# Light_Board.net
KiCad netlist of a schematic drawn in Altium Designer
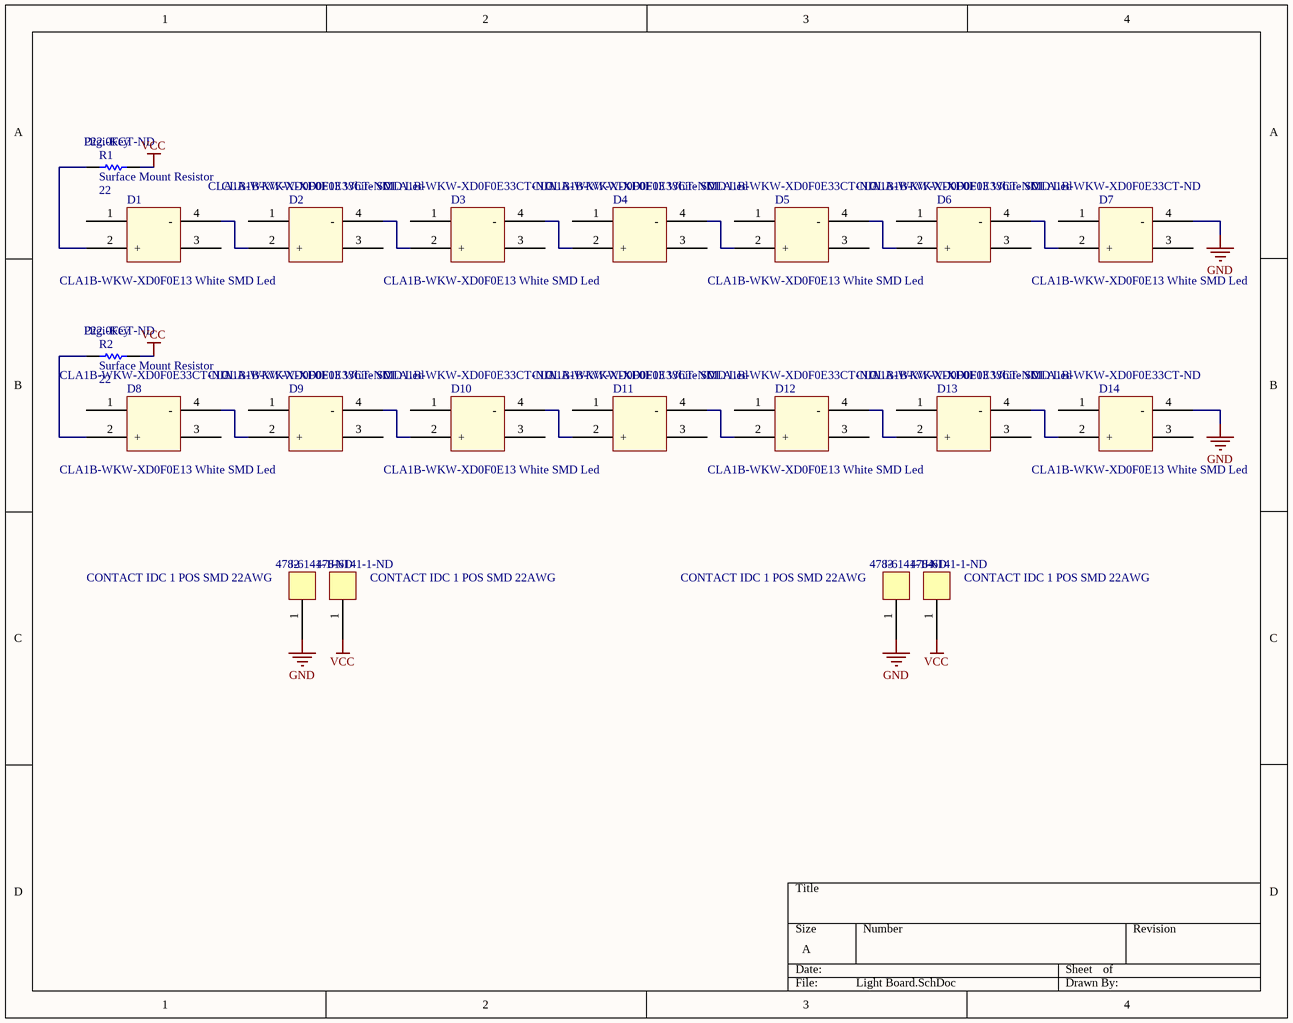
[diagram p0: Light Board.SchDoc]

(export (version "E")
  (design (tool "Eeschema 10.0.6"))
  (components
    (comp (ref "D1")
      (value "CLA1B-WKW-XD0F0E13 White SMD Led")
      (footprint "CLA1B-WKW-XD0F0E13 White SMD Led")
      (libsource (lib "Light Board") (part "CLA1B-WKW-XD0F0E13 White SMD Led"))
    )
    (comp (ref "D2")
      (value "CLA1B-WKW-XD0F0E13 White SMD Led")
      (footprint "CLA1B-WKW-XD0F0E13 White SMD Led")
      (fields (field (name "SUPPLIER PART NUMBER 1") "CLA1B-WKW-XD0F0E33CT-ND"))
      (libsource (lib "Light Board") (part "CLA1B-WKW-XD0F0E13 White SMD Led"))
    )
    (comp (ref "D3")
      (value "CLA1B-WKW-XD0F0E13 White SMD Led")
      (footprint "CLA1B-WKW-XD0F0E13 White SMD Led")
      (fields (field (name "SUPPLIER PART NUMBER 1") "CLA1B-WKW-XD0F0E33CT-ND"))
      (libsource (lib "Light Board") (part "CLA1B-WKW-XD0F0E13 White SMD Led"))
    )
    (comp (ref "D4")
      (value "CLA1B-WKW-XD0F0E13 White SMD Led")
      (footprint "CLA1B-WKW-XD0F0E13 White SMD Led")
      (fields (field (name "SUPPLIER PART NUMBER 1") "CLA1B-WKW-XD0F0E33CT-ND"))
      (libsource (lib "Light Board") (part "CLA1B-WKW-XD0F0E13 White SMD Led"))
    )
    (comp (ref "D5")
      (value "CLA1B-WKW-XD0F0E13 White SMD Led")
      (footprint "CLA1B-WKW-XD0F0E13 White SMD Led")
      (fields (field (name "SUPPLIER PART NUMBER 1") "CLA1B-WKW-XD0F0E33CT-ND"))
      (libsource (lib "Light Board") (part "CLA1B-WKW-XD0F0E13 White SMD Led"))
    )
    (comp (ref "D6")
      (value "CLA1B-WKW-XD0F0E13 White SMD Led")
      (footprint "CLA1B-WKW-XD0F0E13 White SMD Led")
      (fields (field (name "SUPPLIER PART NUMBER 1") "CLA1B-WKW-XD0F0E33CT-ND"))
      (libsource (lib "Light Board") (part "CLA1B-WKW-XD0F0E13 White SMD Led"))
    )
    (comp (ref "D7")
      (value "CLA1B-WKW-XD0F0E13 White SMD Led")
      (footprint "CLA1B-WKW-XD0F0E13 White SMD Led")
      (fields (field (name "SUPPLIER PART NUMBER 1") "CLA1B-WKW-XD0F0E33CT-ND"))
      (libsource (lib "Light Board") (part "CLA1B-WKW-XD0F0E13 White SMD Led"))
    )
    (comp (ref "D8")
      (value "CLA1B-WKW-XD0F0E13 White SMD Led")
      (footprint "CLA1B-WKW-XD0F0E13 White SMD Led")
      (fields (field (name "SUPPLIER PART NUMBER 1") "CLA1B-WKW-XD0F0E33CT-ND"))
      (libsource (lib "Light Board") (part "CLA1B-WKW-XD0F0E13 White SMD Led"))
    )
    (comp (ref "D9")
      (value "CLA1B-WKW-XD0F0E13 White SMD Led")
      (footprint "CLA1B-WKW-XD0F0E13 White SMD Led")
      (fields (field (name "SUPPLIER PART NUMBER 1") "CLA1B-WKW-XD0F0E33CT-ND"))
      (libsource (lib "Light Board") (part "CLA1B-WKW-XD0F0E13 White SMD Led"))
    )
    (comp (ref "D10")
      (value "CLA1B-WKW-XD0F0E13 White SMD Led")
      (footprint "CLA1B-WKW-XD0F0E13 White SMD Led")
      (fields (field (name "SUPPLIER PART NUMBER 1") "CLA1B-WKW-XD0F0E33CT-ND"))
      (libsource (lib "Light Board") (part "CLA1B-WKW-XD0F0E13 White SMD Led"))
    )
    (comp (ref "D11")
      (value "CLA1B-WKW-XD0F0E13 White SMD Led")
      (footprint "CLA1B-WKW-XD0F0E13 White SMD Led")
      (fields (field (name "SUPPLIER PART NUMBER 1") "CLA1B-WKW-XD0F0E33CT-ND"))
      (libsource (lib "Light Board") (part "CLA1B-WKW-XD0F0E13 White SMD Led"))
    )
    (comp (ref "D12")
      (value "CLA1B-WKW-XD0F0E13 White SMD Led")
      (footprint "CLA1B-WKW-XD0F0E13 White SMD Led")
      (fields (field (name "SUPPLIER PART NUMBER 1") "CLA1B-WKW-XD0F0E33CT-ND"))
      (libsource (lib "Light Board") (part "CLA1B-WKW-XD0F0E13 White SMD Led"))
    )
    (comp (ref "D13")
      (value "CLA1B-WKW-XD0F0E13 White SMD Led")
      (footprint "CLA1B-WKW-XD0F0E13 White SMD Led")
      (fields (field (name "SUPPLIER PART NUMBER 1") "CLA1B-WKW-XD0F0E33CT-ND"))
      (libsource (lib "Light Board") (part "CLA1B-WKW-XD0F0E13 White SMD Led"))
    )
    (comp (ref "D14")
      (value "CLA1B-WKW-XD0F0E13 White SMD Led")
      (footprint "CLA1B-WKW-XD0F0E13 White SMD Led")
      (fields (field (name "SUPPLIER PART NUMBER 1") "CLA1B-WKW-XD0F0E33CT-ND"))
      (libsource (lib "Light Board") (part "CLA1B-WKW-XD0F0E13 White SMD Led"))
    )
    (comp (ref "J1")
      (value "CONTACT IDC 1 POS SMD 22AWG")
      (footprint "CONTACT IDC 1 POS SMD 22AWG")
      (fields (field (name "SUPPLIER PART NUMBER 1") "478-6141-1-ND"))
      (libsource (lib "Light Board") (part "CONTACT IDC 1 POS SMD 22AWG"))
    )
    (comp (ref "J2")
      (value "CONTACT IDC 1 POS SMD 22AWG")
      (footprint "CONTACT IDC 1 POS SMD 22AWG")
      (fields (field (name "SUPPLIER PART NUMBER 1") "478-6141-1-ND"))
      (libsource (lib "Light Board") (part "CONTACT IDC 1 POS SMD 22AWG"))
    )
    (comp (ref "J3")
      (value "CONTACT IDC 1 POS SMD 22AWG")
      (footprint "CONTACT IDC 1 POS SMD 22AWG")
      (fields (field (name "SUPPLIER PART NUMBER 1") "478-6141-1-ND"))
      (libsource (lib "Light Board") (part "CONTACT IDC 1 POS SMD 22AWG"))
    )
    (comp (ref "J4")
      (value "CONTACT IDC 1 POS SMD 22AWG")
      (footprint "CONTACT IDC 1 POS SMD 22AWG")
      (fields (field (name "SUPPLIER PART NUMBER 1") "478-6141-1-ND"))
      (libsource (lib "Light Board") (part "CONTACT IDC 1 POS SMD 22AWG"))
    )
    (comp (ref "R1")
      (value "Surface Mount Resistor")
      (footprint "8-1206")
      (description "Resistor")
      (fields
        (field (name "ALTIUM_VALUE") "22")
        (field (name "SUPPLIER 1") "Digi-Key")
        (field (name "SUPPLIER PART NUMBER 1") "P22.0FCT-ND")
        (field (name "PUBLISHER") "Altium Limited")
      )
      (libsource (lib "Light Board") (part "Surface Mount Resistor"))
    )
    (comp (ref "R2")
      (value "Surface Mount Resistor")
      (footprint "8-1206")
      (description "Resistor")
      (fields
        (field (name "ALTIUM_VALUE") "22")
        (field (name "SUPPLIER 1") "Digi-Key")
        (field (name "SUPPLIER PART NUMBER 1") "P22.0FCT-ND")
        (field (name "PUBLISHER") "Altium Limited")
      )
      (libsource (lib "Light Board") (part "Surface Mount Resistor"))
    )
  )
  (nets
    (net (code "1") (name "GND") (class "Default")
      (node (ref "D14") (pin "4") (pinfunction "-_4") (pintype "passive"))
      (node (ref "D7") (pin "4") (pinfunction "-_4") (pintype "passive"))
      (node (ref "J2") (pin "1") (pinfunction "1_1") (pintype "passive"))
      (node (ref "J3") (pin "1") (pinfunction "1_1") (pintype "passive"))
    )
    (net (code "2") (name "Net-(D1-+)") (class "Default")
      (node (ref "D1") (pin "2") (pinfunction "+_2") (pintype "passive"))
      (node (ref "R1") (pin "1") (pinfunction "1_1") (pintype "passive"))
    )
    (net (code "3") (name "Net-(D1--)") (class "Default")
      (node (ref "D1") (pin "4") (pinfunction "-_4") (pintype "passive"))
      (node (ref "D2") (pin "2") (pinfunction "+_2") (pintype "passive"))
    )
    (net (code "4") (name "Net-(D2--)") (class "Default")
      (node (ref "D2") (pin "4") (pinfunction "-_4") (pintype "passive"))
      (node (ref "D3") (pin "2") (pinfunction "+_2") (pintype "passive"))
    )
    (net (code "5") (name "Net-(D3--)") (class "Default")
      (node (ref "D3") (pin "4") (pinfunction "-_4") (pintype "passive"))
      (node (ref "D4") (pin "2") (pinfunction "+_2") (pintype "passive"))
    )
    (net (code "6") (name "Net-(D4--)") (class "Default")
      (node (ref "D4") (pin "4") (pinfunction "-_4") (pintype "passive"))
      (node (ref "D5") (pin "2") (pinfunction "+_2") (pintype "passive"))
    )
    (net (code "7") (name "Net-(D5--)") (class "Default")
      (node (ref "D5") (pin "4") (pinfunction "-_4") (pintype "passive"))
      (node (ref "D6") (pin "2") (pinfunction "+_2") (pintype "passive"))
    )
    (net (code "8") (name "Net-(D6--)") (class "Default")
      (node (ref "D6") (pin "4") (pinfunction "-_4") (pintype "passive"))
      (node (ref "D7") (pin "2") (pinfunction "+_2") (pintype "passive"))
    )
    (net (code "9") (name "Net-(D8-+)") (class "Default")
      (node (ref "D8") (pin "2") (pinfunction "+_2") (pintype "passive"))
      (node (ref "R2") (pin "1") (pinfunction "1_1") (pintype "passive"))
    )
    (net (code "10") (name "Net-(D8--)") (class "Default")
      (node (ref "D8") (pin "4") (pinfunction "-_4") (pintype "passive"))
      (node (ref "D9") (pin "2") (pinfunction "+_2") (pintype "passive"))
    )
    (net (code "11") (name "Net-(D10-+)") (class "Default")
      (node (ref "D10") (pin "2") (pinfunction "+_2") (pintype "passive"))
      (node (ref "D9") (pin "4") (pinfunction "-_4") (pintype "passive"))
    )
    (net (code "12") (name "Net-(D10--)") (class "Default")
      (node (ref "D10") (pin "4") (pinfunction "-_4") (pintype "passive"))
      (node (ref "D11") (pin "2") (pinfunction "+_2") (pintype "passive"))
    )
    (net (code "13") (name "Net-(D11--)") (class "Default")
      (node (ref "D11") (pin "4") (pinfunction "-_4") (pintype "passive"))
      (node (ref "D12") (pin "2") (pinfunction "+_2") (pintype "passive"))
    )
    (net (code "14") (name "Net-(D12--)") (class "Default")
      (node (ref "D12") (pin "4") (pinfunction "-_4") (pintype "passive"))
      (node (ref "D13") (pin "2") (pinfunction "+_2") (pintype "passive"))
    )
    (net (code "15") (name "Net-(D13--)") (class "Default")
      (node (ref "D13") (pin "4") (pinfunction "-_4") (pintype "passive"))
      (node (ref "D14") (pin "2") (pinfunction "+_2") (pintype "passive"))
    )
    (net (code "16") (name "VCC") (class "Default")
      (node (ref "J1") (pin "1") (pinfunction "1_1") (pintype "passive"))
      (node (ref "J4") (pin "1") (pinfunction "1_1") (pintype "passive"))
      (node (ref "R1") (pin "2") (pinfunction "2_2") (pintype "passive"))
      (node (ref "R2") (pin "2") (pinfunction "2_2") (pintype "passive"))
    )
    (net (code "17") (name "unconnected-(D1-5-Pad1)") (class "Default")
      (node (ref "D1") (pin "1") (pinfunction "5_1") (pintype "passive"))
    )
    (net (code "18") (name "unconnected-(D1-Pad3)") (class "Default")
      (node (ref "D1") (pin "3") (pinfunction "3_3") (pintype "passive"))
    )
    (net (code "19") (name "unconnected-(D2-5-Pad1)") (class "Default")
      (node (ref "D2") (pin "1") (pinfunction "5_1") (pintype "passive"))
    )
    (net (code "20") (name "unconnected-(D2-Pad3)") (class "Default")
      (node (ref "D2") (pin "3") (pinfunction "3_3") (pintype "passive"))
    )
    (net (code "21") (name "unconnected-(D3-5-Pad1)") (class "Default")
      (node (ref "D3") (pin "1") (pinfunction "5_1") (pintype "passive"))
    )
    (net (code "22") (name "unconnected-(D3-Pad3)") (class "Default")
      (node (ref "D3") (pin "3") (pinfunction "3_3") (pintype "passive"))
    )
    (net (code "23") (name "unconnected-(D4-5-Pad1)") (class "Default")
      (node (ref "D4") (pin "1") (pinfunction "5_1") (pintype "passive"))
    )
    (net (code "24") (name "unconnected-(D4-Pad3)") (class "Default")
      (node (ref "D4") (pin "3") (pinfunction "3_3") (pintype "passive"))
    )
    (net (code "25") (name "unconnected-(D5-5-Pad1)") (class "Default")
      (node (ref "D5") (pin "1") (pinfunction "5_1") (pintype "passive"))
    )
    (net (code "26") (name "unconnected-(D5-Pad3)") (class "Default")
      (node (ref "D5") (pin "3") (pinfunction "3_3") (pintype "passive"))
    )
    (net (code "27") (name "unconnected-(D6-5-Pad1)") (class "Default")
      (node (ref "D6") (pin "1") (pinfunction "5_1") (pintype "passive"))
    )
    (net (code "28") (name "unconnected-(D6-Pad3)") (class "Default")
      (node (ref "D6") (pin "3") (pinfunction "3_3") (pintype "passive"))
    )
    (net (code "29") (name "unconnected-(D7-5-Pad1)") (class "Default")
      (node (ref "D7") (pin "1") (pinfunction "5_1") (pintype "passive"))
    )
    (net (code "30") (name "unconnected-(D7-Pad3)") (class "Default")
      (node (ref "D7") (pin "3") (pinfunction "3_3") (pintype "passive"))
    )
    (net (code "31") (name "unconnected-(D8-5-Pad1)") (class "Default")
      (node (ref "D8") (pin "1") (pinfunction "5_1") (pintype "passive"))
    )
    (net (code "32") (name "unconnected-(D8-Pad3)") (class "Default")
      (node (ref "D8") (pin "3") (pinfunction "3_3") (pintype "passive"))
    )
    (net (code "33") (name "unconnected-(D9-5-Pad1)") (class "Default")
      (node (ref "D9") (pin "1") (pinfunction "5_1") (pintype "passive"))
    )
    (net (code "34") (name "unconnected-(D9-Pad3)") (class "Default")
      (node (ref "D9") (pin "3") (pinfunction "3_3") (pintype "passive"))
    )
    (net (code "35") (name "unconnected-(D10-5-Pad1)") (class "Default")
      (node (ref "D10") (pin "1") (pinfunction "5_1") (pintype "passive"))
    )
    (net (code "36") (name "unconnected-(D10-Pad3)") (class "Default")
      (node (ref "D10") (pin "3") (pinfunction "3_3") (pintype "passive"))
    )
    (net (code "37") (name "unconnected-(D11-5-Pad1)") (class "Default")
      (node (ref "D11") (pin "1") (pinfunction "5_1") (pintype "passive"))
    )
    (net (code "38") (name "unconnected-(D11-Pad3)") (class "Default")
      (node (ref "D11") (pin "3") (pinfunction "3_3") (pintype "passive"))
    )
    (net (code "39") (name "unconnected-(D12-5-Pad1)") (class "Default")
      (node (ref "D12") (pin "1") (pinfunction "5_1") (pintype "passive"))
    )
    (net (code "40") (name "unconnected-(D12-Pad3)") (class "Default")
      (node (ref "D12") (pin "3") (pinfunction "3_3") (pintype "passive"))
    )
    (net (code "41") (name "unconnected-(D13-5-Pad1)") (class "Default")
      (node (ref "D13") (pin "1") (pinfunction "5_1") (pintype "passive"))
    )
    (net (code "42") (name "unconnected-(D13-Pad3)") (class "Default")
      (node (ref "D13") (pin "3") (pinfunction "3_3") (pintype "passive"))
    )
    (net (code "43") (name "unconnected-(D14-5-Pad1)") (class "Default")
      (node (ref "D14") (pin "1") (pinfunction "5_1") (pintype "passive"))
    )
    (net (code "44") (name "unconnected-(D14-Pad3)") (class "Default")
      (node (ref "D14") (pin "3") (pinfunction "3_3") (pintype "passive"))
    )
  )
)
